# Sensor_with_button.net
KiCad netlist of a schematic drawn in EAGLE
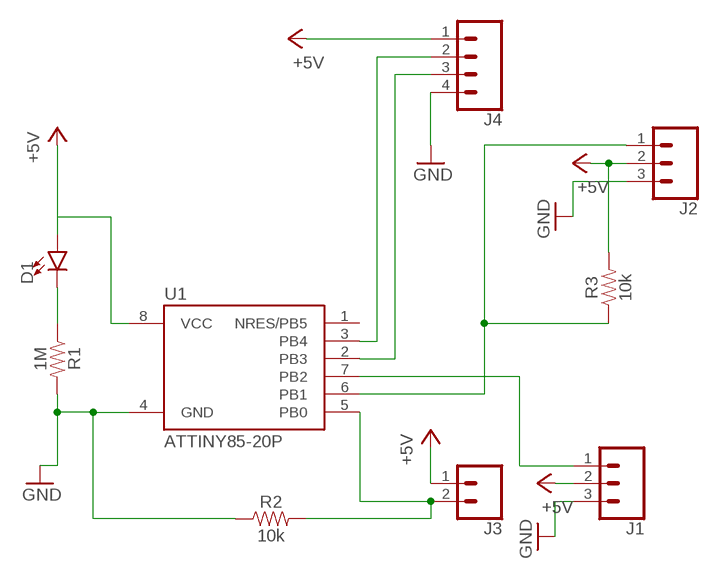
[diagram p0: schematic, sheet 1]

(export (version "E")
  (design (tool "Eeschema 10.0.6"))
  (components
    (comp (ref "D1")
      (value "LED3MM")
      (footprint "eagle-import:LED_3MM")
      (libsource (lib "eagle-import") (part "LED3MM"))
    )
    (comp (ref "J1")
      (value "CONN_03")
      (footprint "eagle-import:1X03")
      (libsource (lib "eagle-import") (part "CONN_03"))
    )
    (comp (ref "J2")
      (value "CONN_03")
      (footprint "eagle-import:1X03")
      (libsource (lib "eagle-import") (part "CONN_03"))
    )
    (comp (ref "J3")
      (value "CONN_02")
      (footprint "eagle-import:1X02")
      (libsource (lib "eagle-import") (part "CONN_02"))
    )
    (comp (ref "J4")
      (value "CONN_04")
      (footprint "eagle-import:1X04")
      (libsource (lib "eagle-import") (part "CONN_04"))
    )
    (comp (ref "R1")
      (value "1M")
      (footprint "eagle-import:AXIAL-0.3")
      (libsource (lib "eagle-import") (part "1MOHM-HORIZ-1/4W-5%"))
    )
    (comp (ref "R2")
      (value "10k")
      (footprint "eagle-import:AXIAL-0.3")
      (libsource (lib "eagle-import") (part "10KOHM-HORIZ-1/4W-1%"))
    )
    (comp (ref "R3")
      (value "10k")
      (footprint "eagle-import:AXIAL-0.3")
      (libsource (lib "eagle-import") (part "10KOHM-HORIZ-1/4W-1%"))
    )
    (comp (ref "U1")
      (value "ATTINY85-20P")
      (footprint "eagle-import:PDIP08_300MIL")
      (libsource (lib "eagle-import") (part "ATTINY85P-20"))
    )
  )
  (nets
    (net (code "1") (name "+5V") (class "Default")
      (node (ref "D1") (pin "A") (pinfunction "A_A") (pintype "passive"))
      (node (ref "J1") (pin "2") (pinfunction "2_2") (pintype "passive"))
      (node (ref "J2") (pin "2") (pinfunction "2_2") (pintype "passive"))
      (node (ref "J3") (pin "1") (pinfunction "1_1") (pintype "passive"))
      (node (ref "J4") (pin "1") (pinfunction "1_1") (pintype "passive"))
      (node (ref "R3") (pin "P$2") (pinfunction "2_P$2") (pintype "passive"))
      (node (ref "U1") (pin "8") (pinfunction "VCC_8") (pintype "power_in"))
    )
    (net (code "2") (name "GND") (class "Default")
      (node (ref "J1") (pin "3") (pinfunction "3_3") (pintype "passive"))
      (node (ref "J2") (pin "3") (pinfunction "3_3") (pintype "passive"))
      (node (ref "J4") (pin "4") (pinfunction "4_4") (pintype "passive"))
      (node (ref "R1") (pin "P$2") (pinfunction "2_P$2") (pintype "passive"))
      (node (ref "R2") (pin "P$1") (pinfunction "1_P$1") (pintype "passive"))
      (node (ref "U1") (pin "4") (pinfunction "GND_4") (pintype "power_in"))
    )
    (net (code "3") (name "Net-(D1-C)") (class "Default")
      (node (ref "D1") (pin "K") (pinfunction "C_K") (pintype "passive"))
      (node (ref "R1") (pin "P$1") (pinfunction "1_P$1") (pintype "passive"))
    )
    (net (code "4") (name "Net-(R2-2)") (class "Default")
      (node (ref "J3") (pin "2") (pinfunction "2_2") (pintype "passive"))
      (node (ref "R2") (pin "P$2") (pinfunction "2_P$2") (pintype "passive"))
      (node (ref "U1") (pin "5") (pinfunction "PB0_5") (pintype "bidirectional"))
    )
    (net (code "5") (name "Net-(R3-1)") (class "Default")
      (node (ref "J2") (pin "1") (pinfunction "1_1") (pintype "passive"))
      (node (ref "R3") (pin "P$1") (pinfunction "1_P$1") (pintype "passive"))
      (node (ref "U1") (pin "6") (pinfunction "PB1_6") (pintype "bidirectional"))
    )
    (net (code "6") (name "Net-(U1-PB2)") (class "Default")
      (node (ref "J1") (pin "1") (pinfunction "1_1") (pintype "passive"))
      (node (ref "U1") (pin "7") (pinfunction "PB2_7") (pintype "bidirectional"))
    )
    (net (code "7") (name "Net-(U1-PB3)") (class "Default")
      (node (ref "J4") (pin "3") (pinfunction "3_3") (pintype "passive"))
      (node (ref "U1") (pin "2") (pinfunction "PB3_2") (pintype "bidirectional"))
    )
    (net (code "8") (name "Net-(U1-PB4)") (class "Default")
      (node (ref "J4") (pin "2") (pinfunction "2_2") (pintype "passive"))
      (node (ref "U1") (pin "3") (pinfunction "PB4_3") (pintype "bidirectional"))
    )
    (net (code "9") (name "unconnected-(U1-NRES{slash}PB5-Pad1)") (class "Default")
      (node (ref "U1") (pin "1") (pinfunction "NRES/PB5_1") (pintype "bidirectional"))
    )
  )
)
